# GSM.net
KiCad netlist of a schematic drawn in Altium Designer
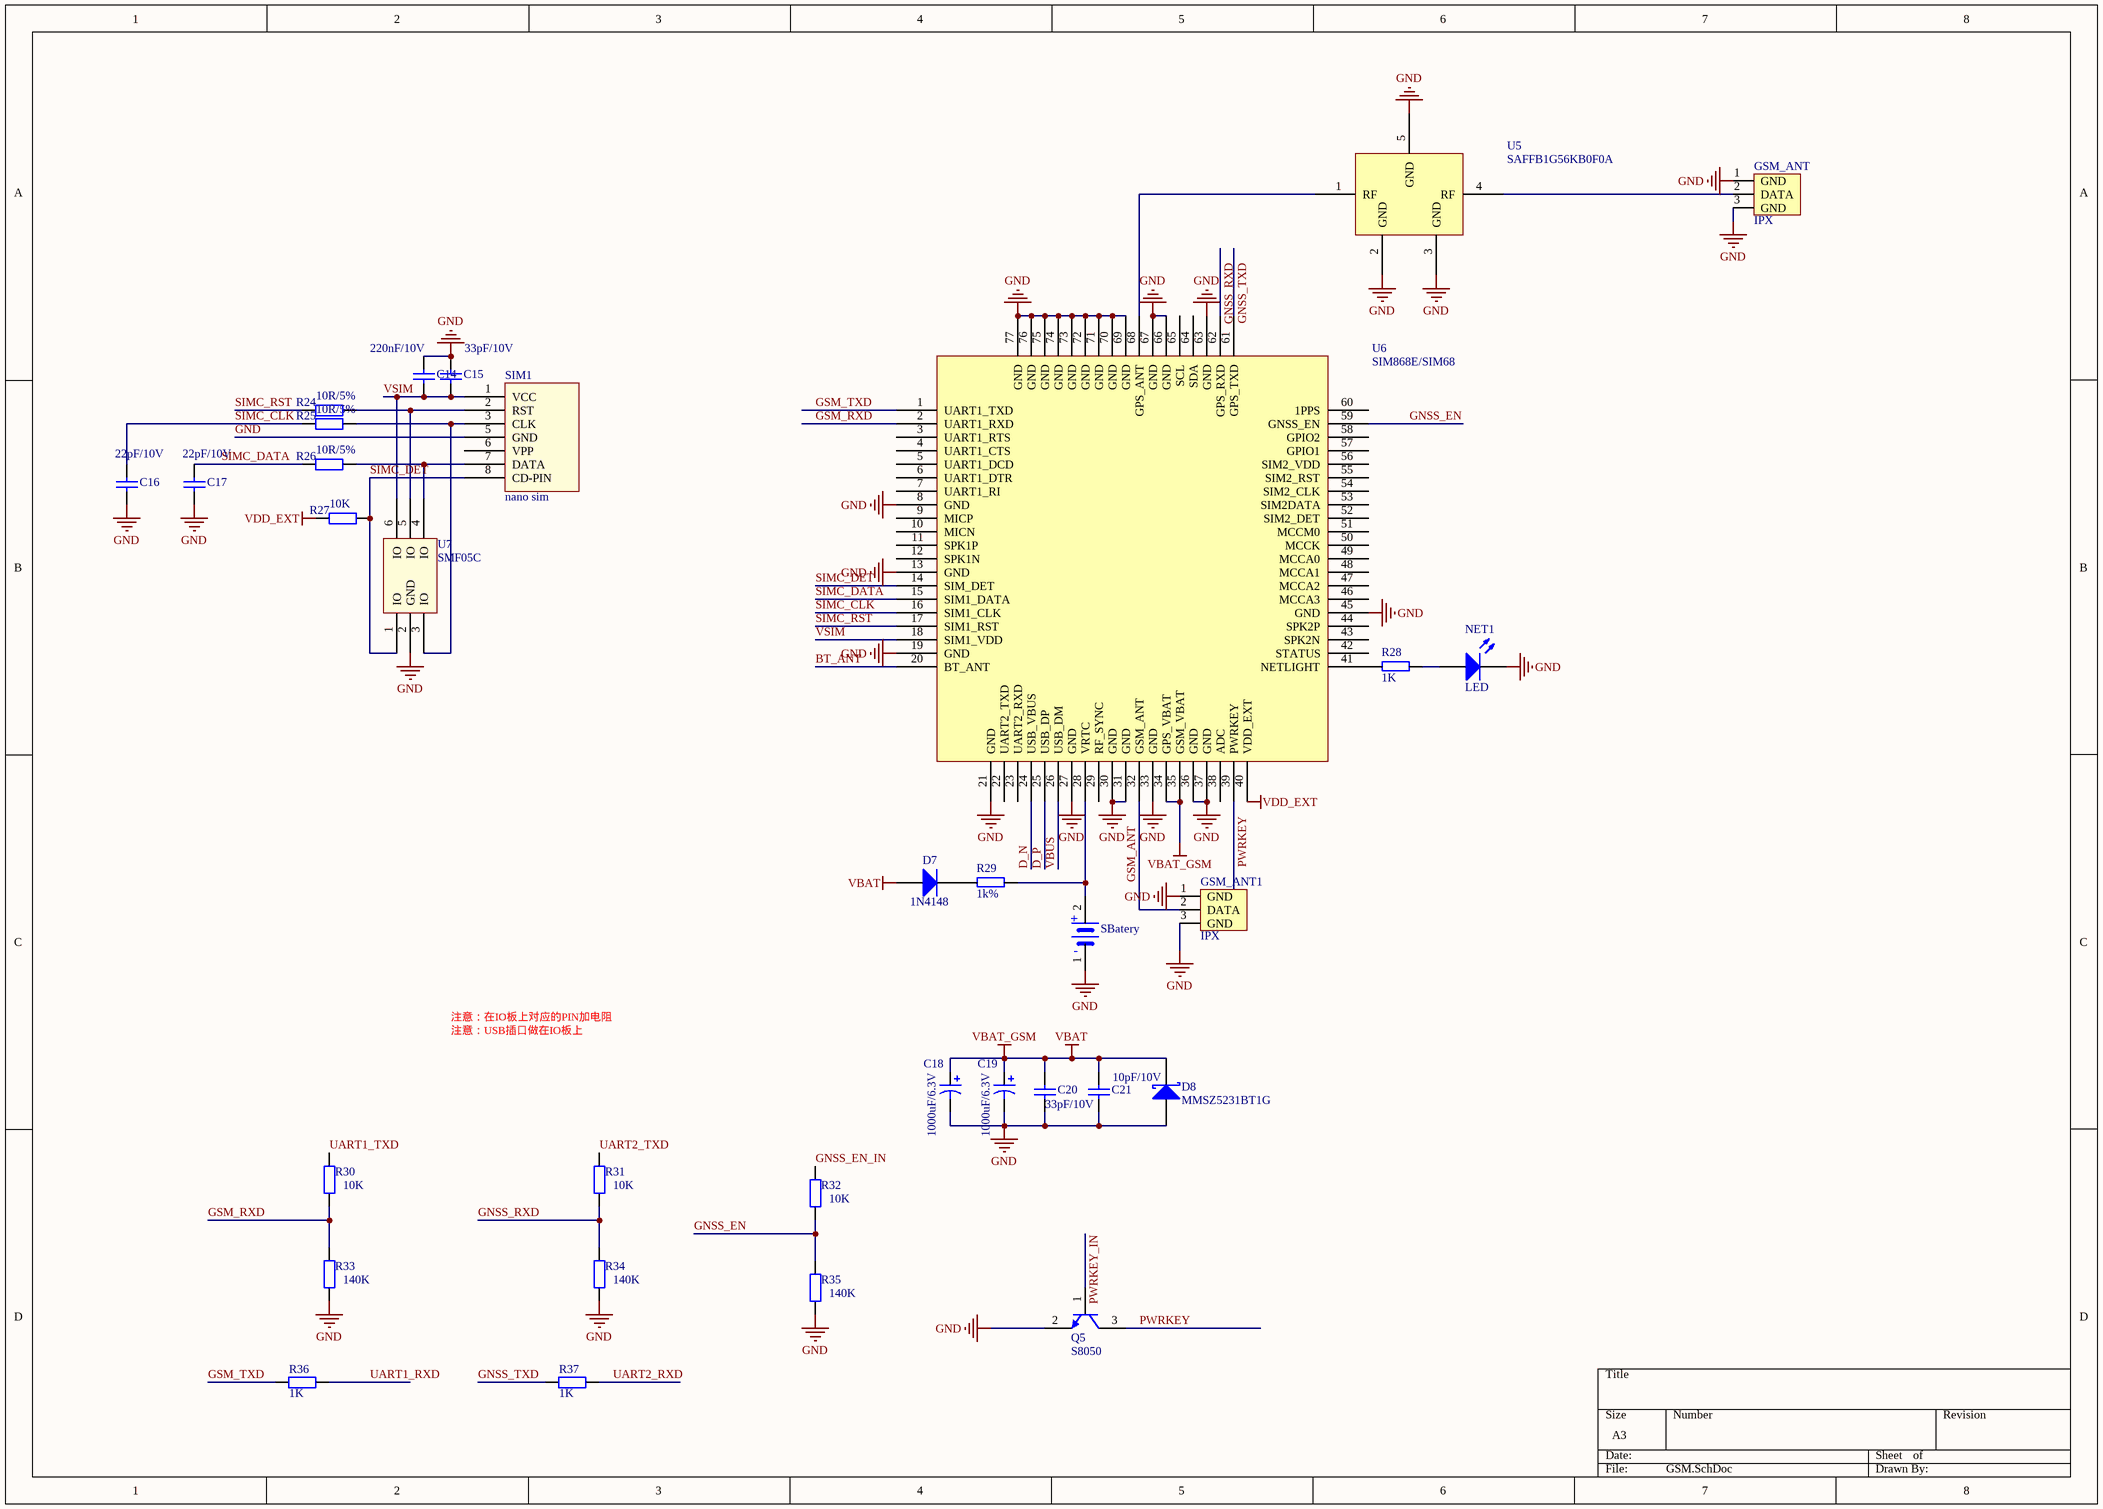
[diagram p0: GSM.SchDoc]

(export (version "E")
  (design (tool "Eeschema 10.0.6"))
  (components
    (comp (ref "C14")
      (value "220nF/10V")
      (footprint "0402C")
      (description "Capacitor")
      (fields (field (name "PUBLISHER") "Altium Limited"))
      (libsource (lib "Miscellaneous Devices") (part "Cap"))
    )
    (comp (ref "C15")
      (value "33pF/10V")
      (footprint "0402C")
      (description "Capacitor")
      (fields (field (name "PUBLISHER") "Altium Limited"))
      (libsource (lib "Miscellaneous Devices") (part "Cap"))
    )
    (comp (ref "C16")
      (value "22pF/10V")
      (footprint "0402C")
      (description "Capacitor")
      (fields (field (name "PUBLISHER") "Altium Limited"))
      (libsource (lib "Miscellaneous Devices") (part "Cap"))
    )
    (comp (ref "C17")
      (value "22pF/10V")
      (footprint "0402C")
      (description "Capacitor")
      (fields (field (name "PUBLISHER") "Altium Limited"))
      (libsource (lib "Miscellaneous Devices") (part "Cap"))
    )
    (comp (ref "C18")
      (value "1000uF/6.3V")
      (footprint "7343")
      (description "Polarized Capacitor (Radial)")
      (fields (field (name "PUBLISHER") "Altium Limited"))
      (libsource (lib "Miscellaneous Devices") (part "Cap Pol1"))
    )
    (comp (ref "C19")
      (value "1000uF/6.3V")
      (footprint "7343")
      (description "Polarized Capacitor (Radial)")
      (fields (field (name "PUBLISHER") "Altium Limited"))
      (libsource (lib "Miscellaneous Devices") (part "Cap Pol1"))
    )
    (comp (ref "C20")
      (value "33pF/10V")
      (footprint "0402C")
      (description "Capacitor")
      (fields (field (name "PUBLISHER") "Altium Limited"))
      (libsource (lib "Miscellaneous Devices") (part "Cap"))
    )
    (comp (ref "C21")
      (value "10pF/10V")
      (footprint "0402C")
      (description "Capacitor")
      (fields (field (name "PUBLISHER") "Altium Limited"))
      (libsource (lib "Miscellaneous Devices") (part "Cap"))
    )
    (comp (ref "D7")
      (value "1N4148")
      (footprint "sod323")
      (description "High Conductance Fast Diode")
      (fields (field (name "PUBLISHER") "Altium Limited"))
      (libsource (lib "Miscellaneous Devices") (part "Diode 1N4148"))
    )
    (comp (ref "D8")
      (value "MMSZ5231BT1G")
      (footprint "SOD123")
      (description "Schottky Rectifier")
      (fields (field (name "PUBLISHER") "Altium Limited"))
      (libsource (lib "Miscellaneous Devices") (part "Diode 10TQ040"))
    )
    (comp (ref "GSM_ANT")
      (value "IPX")
      (footprint "IPX")
      (description "IPEX座")
      (libsource (lib "SIM800C 原理图库") (part "IPEX"))
    )
    (comp (ref "GSM_ANT1")
      (value "IPX")
      (footprint "IPX")
      (description "IPEX座")
      (libsource (lib "SIM800C 原理图库") (part "IPEX"))
    )
    (comp (ref "NET1")
      (value "LED")
      (footprint "0603LED")
      (description "Typical RED, GREEN, YELLOW, AMBER GaAs LED")
      (fields (field (name "PUBLISHER") "Altium Limited"))
      (libsource (lib "SIM800C 原理图库") (part "LED2"))
    )
    (comp (ref "Q5") (value "S8050") (footprint "SOT23-3") (libsource (lib "Schlib1") (part "NPN")))
    (comp (ref "R24")
      (value "10R/5%")
      (footprint "0402R")
      (description "Resistor")
      (fields (field (name "PUBLISHER") "Altium Limited"))
      (libsource (lib "") (part "Res2_1"))
    )
    (comp (ref "R25")
      (value "10R/5%")
      (footprint "0402R")
      (description "Resistor")
      (fields (field (name "PUBLISHER") "Altium Limited"))
      (libsource (lib "") (part "Res2_1"))
    )
    (comp (ref "R26")
      (value "10R/5%")
      (footprint "0402R")
      (description "Resistor")
      (fields (field (name "PUBLISHER") "Altium Limited"))
      (libsource (lib "") (part "Res2_1"))
    )
    (comp (ref "R27")
      (value "10K")
      (footprint "0402R")
      (description "Resistor")
      (fields (field (name "PUBLISHER") "Altium Limited"))
      (libsource (lib "") (part "Res2_1"))
    )
    (comp (ref "R28") (value "1K") (footprint "0402R") (libsource (lib "SIM800C 原理图库") (part "R")))
    (comp (ref "R29") (value "1k%") (footprint "0402R") (libsource (lib "SIM800C 原理图库") (part "R")))
    (comp (ref "R30")
      (value "10K")
      (footprint "0402R")
      (description "Resistor")
      (fields (field (name "PUBLISHER") "Altium Limited"))
      (libsource (lib "Miscellaneous Devices") (part "Res2"))
    )
    (comp (ref "R31")
      (value "10K")
      (footprint "0402R")
      (description "Resistor")
      (fields (field (name "PUBLISHER") "Altium Limited"))
      (libsource (lib "Miscellaneous Devices") (part "Res2"))
    )
    (comp (ref "R32")
      (value "10K")
      (footprint "0402R")
      (description "Resistor")
      (fields (field (name "PUBLISHER") "Altium Limited"))
      (libsource (lib "Miscellaneous Devices") (part "Res2"))
    )
    (comp (ref "R33")
      (value "140K")
      (footprint "0402R")
      (description "Resistor")
      (fields (field (name "PUBLISHER") "Altium Limited"))
      (libsource (lib "Miscellaneous Devices") (part "Res2"))
    )
    (comp (ref "R34")
      (value "140K")
      (footprint "0402R")
      (description "Resistor")
      (fields (field (name "PUBLISHER") "Altium Limited"))
      (libsource (lib "Miscellaneous Devices") (part "Res2"))
    )
    (comp (ref "R35")
      (value "140K")
      (footprint "0402R")
      (description "Resistor")
      (fields (field (name "PUBLISHER") "Altium Limited"))
      (libsource (lib "Miscellaneous Devices") (part "Res2"))
    )
    (comp (ref "R36")
      (value "1K")
      (footprint "0402R")
      (description "Resistor")
      (fields (field (name "PUBLISHER") "Altium Limited"))
      (libsource (lib "") (part "Res2_2"))
    )
    (comp (ref "R37")
      (value "1K")
      (footprint "0402R")
      (description "Resistor")
      (fields (field (name "PUBLISHER") "Altium Limited"))
      (libsource (lib "") (part "Res2_2"))
    )
    (comp (ref "SBatery")
      (value "SBatery")
      (footprint "MS621FE")
      (libsource (lib "Myself_1") (part "SBatery"))
    )
    (comp (ref "SIM1") (value "nano sim") (footprint "Nano SIM") (libsource (lib "lm") (part "nano sim")))
    (comp (ref "U5")
      (value "SAFFB1G56KB0F0A")
      (footprint "SAFFB1G56KB0F0A")
      (libsource (lib "stm32") (part "SAFFB1G56KBOFA"))
    )
    (comp (ref "U6")
      (value "SIM868E/SIM68")
      (footprint "SIM868")
      (libsource (lib "stm32") (part "SIM868E/SIM868"))
    )
    (comp (ref "U7") (value "SMF05C") (footprint "SC70-6L") (libsource (lib "lm") (part "SMF05C")))
  )
  (nets
    (net (code "1") (name "/BT_ANT") (class "Default")
      (node (ref "U6") (pin "20") (pinfunction "BT_ANT_20") (pintype "passive"))
    )
    (net (code "2") (name "/D_N") (class "Default")
      (node (ref "U6") (pin "24") (pinfunction "USB_VBUS_24") (pintype "passive"))
    )
    (net (code "3") (name "/D_P") (class "Default")
      (node (ref "U6") (pin "25") (pinfunction "USB_DP_25") (pintype "passive"))
    )
    (net (code "4") (name "/GNSS_EN") (class "Default")
      (node (ref "R32") (pin "2") (pinfunction "2_2") (pintype "passive"))
      (node (ref "R35") (pin "1") (pinfunction "1_1") (pintype "passive"))
      (node (ref "U6") (pin "59") (pinfunction "GNSS_EN_59") (pintype "passive"))
    )
    (net (code "5") (name "/GNSS_EN_IN") (class "Default")
      (node (ref "R32") (pin "1") (pinfunction "1_1") (pintype "passive"))
    )
    (net (code "6") (name "/GNSS_RXD") (class "Default")
      (node (ref "R31") (pin "2") (pinfunction "2_2") (pintype "passive"))
      (node (ref "R34") (pin "1") (pinfunction "1_1") (pintype "passive"))
      (node (ref "U6") (pin "62") (pinfunction "GPS_RXD_62") (pintype "passive"))
    )
    (net (code "7") (name "/GNSS_TXD") (class "Default")
      (node (ref "R37") (pin "1") (pinfunction "1_1") (pintype "passive"))
      (node (ref "U6") (pin "61") (pinfunction "GPS_TXD_61") (pintype "passive"))
    )
    (net (code "8") (name "/GSM_ANT") (class "Default")
      (node (ref "GSM_ANT1") (pin "2") (pinfunction "DATA_2") (pintype "passive"))
      (node (ref "U6") (pin "32") (pinfunction "GSM_ANT_32") (pintype "passive"))
    )
    (net (code "9") (name "/GSM_RXD") (class "Default")
      (node (ref "R30") (pin "2") (pinfunction "2_2") (pintype "passive"))
      (node (ref "R33") (pin "1") (pinfunction "1_1") (pintype "passive"))
      (node (ref "U6") (pin "2") (pinfunction "UART1_RXD_2") (pintype "passive"))
    )
    (net (code "10") (name "/GSM_TXD") (class "Default")
      (node (ref "R36") (pin "1") (pinfunction "1_1") (pintype "passive"))
      (node (ref "U6") (pin "1") (pinfunction "UART1_TXD_1") (pintype "passive"))
    )
    (net (code "11") (name "/PWRKEY") (class "Default")
      (node (ref "Q5") (pin "3") (pinfunction "C_3") (pintype "passive"))
      (node (ref "U6") (pin "39") (pinfunction "PWRKEY_39") (pintype "passive"))
    )
    (net (code "12") (name "/PWRKEY_IN") (class "Default")
      (node (ref "Q5") (pin "1") (pinfunction "B_1") (pintype "passive"))
    )
    (net (code "13") (name "/SIMC_CLK") (class "Default")
      (node (ref "C16") (pin "1") (pinfunction "1_1") (pintype "passive"))
      (node (ref "R25") (pin "2") (pinfunction "2_2") (pintype "passive"))
      (node (ref "U6") (pin "16") (pinfunction "SIM1_CLK_16") (pintype "passive"))
    )
    (net (code "14") (name "/SIMC_DATA") (class "Default")
      (node (ref "C17") (pin "1") (pinfunction "1_1") (pintype "passive"))
      (node (ref "R26") (pin "2") (pinfunction "2_2") (pintype "passive"))
      (node (ref "U6") (pin "15") (pinfunction "SIM1_DATA_15") (pintype "passive"))
    )
    (net (code "15") (name "/SIMC_DET") (class "Default")
      (node (ref "R27") (pin "1") (pinfunction "1_1") (pintype "passive"))
      (node (ref "SIM1") (pin "8") (pinfunction "CD-PIN_8") (pintype "passive"))
      (node (ref "U6") (pin "14") (pinfunction "SIM_DET_14") (pintype "passive"))
      (node (ref "U7") (pin "1") (pinfunction "IO_1") (pintype "passive"))
    )
    (net (code "16") (name "/SIMC_RST") (class "Default")
      (node (ref "R24") (pin "2") (pinfunction "2_2") (pintype "passive"))
      (node (ref "U6") (pin "17") (pinfunction "SIM1_RST_17") (pintype "passive"))
    )
    (net (code "17") (name "/UART1_RXD") (class "Default")
      (node (ref "R36") (pin "2") (pinfunction "2_2") (pintype "passive"))
    )
    (net (code "18") (name "/UART1_TXD") (class "Default")
      (node (ref "R30") (pin "1") (pinfunction "1_1") (pintype "passive"))
    )
    (net (code "19") (name "/UART2_RXD") (class "Default")
      (node (ref "R37") (pin "2") (pinfunction "2_2") (pintype "passive"))
    )
    (net (code "20") (name "/UART2_TXD") (class "Default")
      (node (ref "R31") (pin "1") (pinfunction "1_1") (pintype "passive"))
    )
    (net (code "21") (name "/VBUS") (class "Default")
      (node (ref "U6") (pin "26") (pinfunction "USB_DM_26") (pintype "passive"))
    )
    (net (code "22") (name "/VSIM") (class "Default")
      (node (ref "C14") (pin "2") (pinfunction "2_2") (pintype "passive"))
      (node (ref "C15") (pin "2") (pinfunction "2_2") (pintype "passive"))
      (node (ref "SIM1") (pin "1") (pinfunction "VCC_1") (pintype "passive"))
      (node (ref "U6") (pin "18") (pinfunction "SIM1_VDD_18") (pintype "passive"))
      (node (ref "U7") (pin "6") (pinfunction "IO_6") (pintype "passive"))
    )
    (net (code "23") (name "GND") (class "Default")
      (node (ref "C14") (pin "1") (pinfunction "1_1") (pintype "passive"))
      (node (ref "C15") (pin "1") (pinfunction "1_1") (pintype "passive"))
      (node (ref "C16") (pin "2") (pinfunction "2_2") (pintype "passive"))
      (node (ref "C17") (pin "2") (pinfunction "2_2") (pintype "passive"))
      (node (ref "C18") (pin "2") (pinfunction "2_2") (pintype "passive"))
      (node (ref "C19") (pin "2") (pinfunction "2_2") (pintype "passive"))
      (node (ref "C20") (pin "2") (pinfunction "2_2") (pintype "passive"))
      (node (ref "C21") (pin "2") (pinfunction "2_2") (pintype "passive"))
      (node (ref "D8") (pin "A") (pinfunction "A_A") (pintype "passive"))
      (node (ref "GSM_ANT") (pin "1") (pinfunction "GND_1") (pintype "passive"))
      (node (ref "GSM_ANT") (pin "3") (pinfunction "GND_3") (pintype "passive"))
      (node (ref "GSM_ANT1") (pin "1") (pinfunction "GND_1") (pintype "passive"))
      (node (ref "GSM_ANT1") (pin "3") (pinfunction "GND_3") (pintype "passive"))
      (node (ref "NET1") (pin "2") (pinfunction "K_2") (pintype "passive"))
      (node (ref "Q5") (pin "2") (pinfunction "E_2") (pintype "passive"))
      (node (ref "R33") (pin "2") (pinfunction "2_2") (pintype "passive"))
      (node (ref "R34") (pin "2") (pinfunction "2_2") (pintype "passive"))
      (node (ref "R35") (pin "2") (pinfunction "2_2") (pintype "passive"))
      (node (ref "SBatery") (pin "1") (pinfunction "1_1") (pintype "passive"))
      (node (ref "SIM1") (pin "5") (pinfunction "GND_5") (pintype "passive"))
      (node (ref "U5") (pin "2") (pinfunction "GND_2") (pintype "passive"))
      (node (ref "U5") (pin "3") (pinfunction "GND_3") (pintype "passive"))
      (node (ref "U5") (pin "5") (pinfunction "GND_5") (pintype "passive"))
      (node (ref "U6") (pin "13") (pinfunction "GND_13") (pintype "passive"))
      (node (ref "U6") (pin "19") (pinfunction "GND_19") (pintype "passive"))
      (node (ref "U6") (pin "21") (pinfunction "GND_21") (pintype "passive"))
      (node (ref "U6") (pin "27") (pinfunction "GND_27") (pintype "passive"))
      (node (ref "U6") (pin "30") (pinfunction "GND_30") (pintype "passive"))
      (node (ref "U6") (pin "31") (pinfunction "GND_31") (pintype "passive"))
      (node (ref "U6") (pin "33") (pinfunction "GND_33") (pintype "passive"))
      (node (ref "U6") (pin "36") (pinfunction "GND_36") (pintype "passive"))
      (node (ref "U6") (pin "37") (pinfunction "GND_37") (pintype "passive"))
      (node (ref "U6") (pin "45") (pinfunction "GND_45") (pintype "passive"))
      (node (ref "U6") (pin "63") (pinfunction "GND_63") (pintype "passive"))
      (node (ref "U6") (pin "66") (pinfunction "GND_66") (pintype "passive"))
      (node (ref "U6") (pin "67") (pinfunction "GND_67") (pintype "passive"))
      (node (ref "U6") (pin "69") (pinfunction "GND_69") (pintype "passive"))
      (node (ref "U6") (pin "70") (pinfunction "GND_70") (pintype "passive"))
      (node (ref "U6") (pin "71") (pinfunction "GND_71") (pintype "passive"))
      (node (ref "U6") (pin "72") (pinfunction "GND_72") (pintype "passive"))
      (node (ref "U6") (pin "73") (pinfunction "GND_73") (pintype "passive"))
      (node (ref "U6") (pin "74") (pinfunction "GND_74") (pintype "passive"))
      (node (ref "U6") (pin "75") (pinfunction "GND_75") (pintype "passive"))
      (node (ref "U6") (pin "76") (pinfunction "GND_76") (pintype "passive"))
      (node (ref "U6") (pin "77") (pinfunction "GND_77") (pintype "passive"))
      (node (ref "U6") (pin "8") (pinfunction "GND_8") (pintype "passive"))
      (node (ref "U7") (pin "2") (pinfunction "GND_2") (pintype "passive"))
    )
    (net (code "24") (name "Net-(D7-PadK)") (class "Default")
      (node (ref "D7") (pin "K") (pinfunction "K_K") (pintype "passive"))
      (node (ref "R29") (pin "2") (pintype "passive"))
    )
    (net (code "25") (name "Net-(GSM_ANT-DATA)") (class "Default")
      (node (ref "GSM_ANT") (pin "2") (pinfunction "DATA_2") (pintype "passive"))
      (node (ref "U5") (pin "4") (pinfunction "RF_4") (pintype "passive"))
    )
    (net (code "26") (name "Net-(NET1-A)") (class "Default")
      (node (ref "NET1") (pin "1") (pinfunction "A_1") (pintype "passive"))
      (node (ref "R28") (pin "1") (pintype "passive"))
    )
    (net (code "27") (name "Net-(SIM1-CLK)") (class "Default")
      (node (ref "R25") (pin "1") (pinfunction "1_1") (pintype "passive"))
      (node (ref "SIM1") (pin "3") (pinfunction "CLK_3") (pintype "passive"))
      (node (ref "U7") (pin "3") (pinfunction "IO_3") (pintype "passive"))
    )
    (net (code "28") (name "Net-(SIM1-DATA)") (class "Default")
      (node (ref "R26") (pin "1") (pinfunction "1_1") (pintype "passive"))
      (node (ref "SIM1") (pin "7") (pinfunction "DATA_7") (pintype "passive"))
      (node (ref "U7") (pin "4") (pinfunction "IO_4") (pintype "passive"))
    )
    (net (code "29") (name "Net-(SIM1-RST)") (class "Default")
      (node (ref "R24") (pin "1") (pinfunction "1_1") (pintype "passive"))
      (node (ref "SIM1") (pin "2") (pinfunction "RST_2") (pintype "passive"))
      (node (ref "U7") (pin "5") (pinfunction "IO_5") (pintype "passive"))
    )
    (net (code "30") (name "Net-(U6-GPS_ANT)") (class "Default")
      (node (ref "U5") (pin "1") (pinfunction "RF_1") (pintype "passive"))
      (node (ref "U6") (pin "68") (pinfunction "GPS_ANT_68") (pintype "passive"))
    )
    (net (code "31") (name "Net-(U6-NETLIGHT)") (class "Default")
      (node (ref "R28") (pin "2") (pintype "passive"))
      (node (ref "U6") (pin "41") (pinfunction "NETLIGHT_41") (pintype "passive"))
    )
    (net (code "32") (name "Net-(U6-VRTC)") (class "Default")
      (node (ref "R29") (pin "1") (pintype "passive"))
      (node (ref "SBatery") (pin "2") (pinfunction "2_2") (pintype "passive"))
      (node (ref "U6") (pin "28") (pinfunction "VRTC_28") (pintype "passive"))
    )
    (net (code "33") (name "VBAT") (class "Default")
      (node (ref "C18") (pin "1") (pinfunction "1_1") (pintype "passive"))
      (node (ref "C19") (pin "1") (pinfunction "1_1") (pintype "passive"))
      (node (ref "C20") (pin "1") (pinfunction "1_1") (pintype "passive"))
      (node (ref "C21") (pin "1") (pinfunction "1_1") (pintype "passive"))
      (node (ref "D7") (pin "A") (pinfunction "A_A") (pintype "passive"))
      (node (ref "D8") (pin "K") (pinfunction "K_K") (pintype "passive"))
      (node (ref "U6") (pin "34") (pinfunction "GPS_VBAT_34") (pintype "passive"))
      (node (ref "U6") (pin "35") (pinfunction "GSM_VBAT_35") (pintype "passive"))
    )
    (net (code "34") (name "VDD_EXT") (class "Default")
      (node (ref "R27") (pin "2") (pinfunction "2_2") (pintype "passive"))
      (node (ref "U6") (pin "40") (pinfunction "VDD_EXT_40") (pintype "passive"))
    )
    (net (code "35") (name "unconnected-(SIM1-VPP-Pad6)") (class "Default")
      (node (ref "SIM1") (pin "6") (pinfunction "VPP_6") (pintype "passive"))
    )
    (net (code "36") (name "unconnected-(U6-1PPS-Pad60)") (class "Default")
      (node (ref "U6") (pin "60") (pinfunction "1PPS_60") (pintype "passive"))
    )
    (net (code "37") (name "unconnected-(U6-ADC-Pad38)") (class "Default")
      (node (ref "U6") (pin "38") (pinfunction "ADC_38") (pintype "passive"))
    )
    (net (code "38") (name "unconnected-(U6-GPIO1-Pad57)") (class "Default")
      (node (ref "U6") (pin "57") (pinfunction "GPIO1_57") (pintype "passive"))
    )
    (net (code "39") (name "unconnected-(U6-GPIO2-Pad58)") (class "Default")
      (node (ref "U6") (pin "58") (pinfunction "GPIO2_58") (pintype "passive"))
    )
    (net (code "40") (name "unconnected-(U6-MCCA0-Pad49)") (class "Default")
      (node (ref "U6") (pin "49") (pinfunction "MCCA0_49") (pintype "passive"))
    )
    (net (code "41") (name "unconnected-(U6-MCCA1-Pad48)") (class "Default")
      (node (ref "U6") (pin "48") (pinfunction "MCCA1_48") (pintype "passive"))
    )
    (net (code "42") (name "unconnected-(U6-MCCA2-Pad47)") (class "Default")
      (node (ref "U6") (pin "47") (pinfunction "MCCA2_47") (pintype "passive"))
    )
    (net (code "43") (name "unconnected-(U6-MCCA3-Pad46)") (class "Default")
      (node (ref "U6") (pin "46") (pinfunction "MCCA3_46") (pintype "passive"))
    )
    (net (code "44") (name "unconnected-(U6-MCCK-Pad50)") (class "Default")
      (node (ref "U6") (pin "50") (pinfunction "MCCK_50") (pintype "passive"))
    )
    (net (code "45") (name "unconnected-(U6-MCCM0-Pad51)") (class "Default")
      (node (ref "U6") (pin "51") (pinfunction "MCCM0_51") (pintype "passive"))
    )
    (net (code "46") (name "unconnected-(U6-MICN-Pad10)") (class "Default")
      (node (ref "U6") (pin "10") (pinfunction "MICN_10") (pintype "passive"))
    )
    (net (code "47") (name "unconnected-(U6-MICP-Pad9)") (class "Default")
      (node (ref "U6") (pin "9") (pinfunction "MICP_9") (pintype "passive"))
    )
    (net (code "48") (name "unconnected-(U6-RF_SYNC-Pad29)") (class "Default")
      (node (ref "U6") (pin "29") (pinfunction "RF_SYNC_29") (pintype "passive"))
    )
    (net (code "49") (name "unconnected-(U6-SCL-Pad65)") (class "Default")
      (node (ref "U6") (pin "65") (pinfunction "SCL_65") (pintype "passive"))
    )
    (net (code "50") (name "unconnected-(U6-SDA-Pad64)") (class "Default")
      (node (ref "U6") (pin "64") (pinfunction "SDA_64") (pintype "passive"))
    )
    (net (code "51") (name "unconnected-(U6-SIM2DATA-Pad53)") (class "Default")
      (node (ref "U6") (pin "53") (pinfunction "SIM2DATA_53") (pintype "passive"))
    )
    (net (code "52") (name "unconnected-(U6-SIM2_CLK-Pad54)") (class "Default")
      (node (ref "U6") (pin "54") (pinfunction "SIM2_CLK_54") (pintype "passive"))
    )
    (net (code "53") (name "unconnected-(U6-SIM2_DET-Pad52)") (class "Default")
      (node (ref "U6") (pin "52") (pinfunction "SIM2_DET_52") (pintype "passive"))
    )
    (net (code "54") (name "unconnected-(U6-SIM2_RST-Pad55)") (class "Default")
      (node (ref "U6") (pin "55") (pinfunction "SIM2_RST_55") (pintype "passive"))
    )
    (net (code "55") (name "unconnected-(U6-SIM2_VDD-Pad56)") (class "Default")
      (node (ref "U6") (pin "56") (pinfunction "SIM2_VDD_56") (pintype "passive"))
    )
    (net (code "56") (name "unconnected-(U6-SPK1N-Pad12)") (class "Default")
      (node (ref "U6") (pin "12") (pinfunction "SPK1N_12") (pintype "passive"))
    )
    (net (code "57") (name "unconnected-(U6-SPK1P-Pad11)") (class "Default")
      (node (ref "U6") (pin "11") (pinfunction "SPK1P_11") (pintype "passive"))
    )
    (net (code "58") (name "unconnected-(U6-SPK2N-Pad43)") (class "Default")
      (node (ref "U6") (pin "43") (pinfunction "SPK2N_43") (pintype "passive"))
    )
    (net (code "59") (name "unconnected-(U6-SPK2P-Pad44)") (class "Default")
      (node (ref "U6") (pin "44") (pinfunction "SPK2P_44") (pintype "passive"))
    )
    (net (code "60") (name "unconnected-(U6-STATUS-Pad42)") (class "Default")
      (node (ref "U6") (pin "42") (pinfunction "STATUS_42") (pintype "passive"))
    )
    (net (code "61") (name "unconnected-(U6-UART1_CTS-Pad4)") (class "Default")
      (node (ref "U6") (pin "4") (pinfunction "UART1_CTS_4") (pintype "passive"))
    )
    (net (code "62") (name "unconnected-(U6-UART1_DCD-Pad5)") (class "Default")
      (node (ref "U6") (pin "5") (pinfunction "UART1_DCD_5") (pintype "passive"))
    )
    (net (code "63") (name "unconnected-(U6-UART1_DTR-Pad6)") (class "Default")
      (node (ref "U6") (pin "6") (pinfunction "UART1_DTR_6") (pintype "passive"))
    )
    (net (code "64") (name "unconnected-(U6-UART1_RI-Pad7)") (class "Default")
      (node (ref "U6") (pin "7") (pinfunction "UART1_RI_7") (pintype "passive"))
    )
    (net (code "65") (name "unconnected-(U6-UART1_RTS-Pad3)") (class "Default")
      (node (ref "U6") (pin "3") (pinfunction "UART1_RTS_3") (pintype "passive"))
    )
    (net (code "66") (name "unconnected-(U6-UART2_RXD-Pad23)") (class "Default")
      (node (ref "U6") (pin "23") (pinfunction "UART2_RXD_23") (pintype "passive"))
    )
    (net (code "67") (name "unconnected-(U6-UART2_TXD-Pad22)") (class "Default")
      (node (ref "U6") (pin "22") (pinfunction "UART2_TXD_22") (pintype "passive"))
    )
  )
)
